# miniPCIE_Connector.net
KiCad netlist of a schematic drawn in Altium Designer
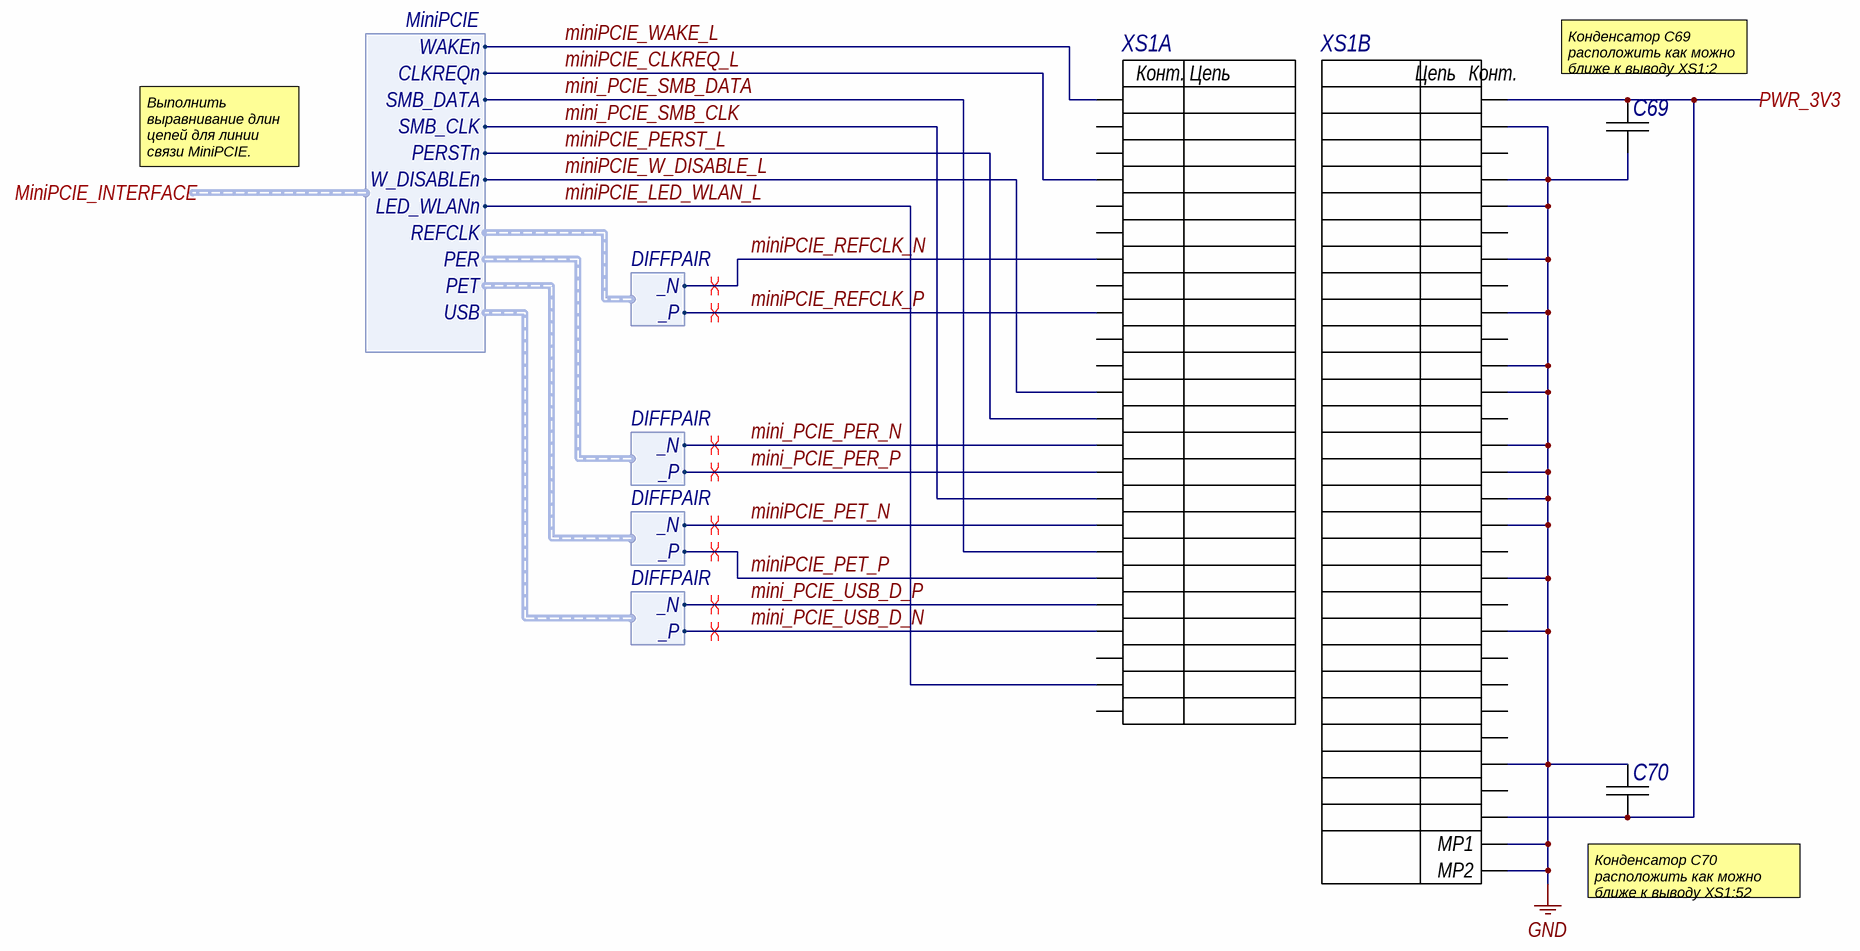
[diagram p0: miniPCIE Connector.SchDoc]

(export (version "E")
  (design (tool "Eeschema 10.0.6"))
  (components
    (comp (ref "C69")
      (value "C1005X7R1E104M")
      (footprint "CAPC1005X55X10LL05")
      (description "Chip Capacitor, 0.1 uF, +/- 20%, 25 V, -55 to 125 degC, 0402 (1005 Metric), RoHS, Tape and Reel")
      (fields (field (name "TOLERANCE") "20%"))
      (libsource (lib "MiniPC DB") (part "CAP_NP"))
    )
    (comp (ref "C70")
      (value "C1005X7R1E104M")
      (footprint "CAPC1005X55X10LL05")
      (description "Chip Capacitor, 0.1 uF, +/- 20%, 25 V, -55 to 125 degC, 0402 (1005 Metric), RoHS, Tape and Reel")
      (fields (field (name "TOLERANCE") "20%"))
      (libsource (lib "MiniPC DB") (part "CAP_NP"))
    )
    (comp (ref "XS1")
      (value "292443-1")
      (footprint "BTB-SM0-8-2H52F")
      (description "Board-to-Board Connector, SMT, Right Angle, Pitch 0.8mm, 52-Position, Female")
      (fields (field (name "PUBLISHER") "Altium"))
      (libsource (lib "MiniPC DB") (part "MINIPCIEXPRESS"))
    )
  )
  (nets
    (net (code "4") (name "/PWR_3V3") (class "Default")
      (node (ref "C69") (pin "2") (pinfunction "2_2") (pintype "passive"))
      (node (ref "C70") (pin "1") (pinfunction "1_1") (pintype "passive"))
      (node (ref "XS1") (pin "2") (pinfunction "3,3Vaux_2") (pintype "passive"))
      (node (ref "XS1") (pin "52") (pinfunction "3,3Vaux_52") (pintype "passive"))
    )
    (net (code "5") (name "/miniPCIE_CLKREQ_L") (class "Default")
      (node (ref "XS1") (pin "7") (pinfunction "CLKREQ#_7") (pintype "passive"))
    )
    (net (code "6") (name "/miniPCIE_LED_WLAN_L") (class "Default")
      (node (ref "XS1") (pin "44") (pinfunction "LED_WLAN#_44") (pintype "passive"))
    )
    (net (code "7") (name "/miniPCIE_PERST_L") (class "Default")
      (node (ref "XS1") (pin "22") (pinfunction "PERST#_22") (pintype "passive"))
    )
    (net (code "8") (name "/miniPCIE_PET_N") (class "Default")
      (node (ref "XS1") (pin "31") (pinfunction "PETnO_31") (pintype "passive"))
    )
    (net (code "9") (name "/miniPCIE_PET_P") (class "Default")
      (node (ref "XS1") (pin "33") (pinfunction "PETpO_33") (pintype "passive"))
    )
    (net (code "10") (name "/miniPCIE_REFCLK_N") (class "Default")
      (node (ref "XS1") (pin "11") (pinfunction "REFCLK-_11") (pintype "passive"))
    )
    (net (code "11") (name "/miniPCIE_REFCLK_P") (class "Default")
      (node (ref "XS1") (pin "13") (pinfunction "REFCLK_+_13") (pintype "passive"))
    )
    (net (code "12") (name "/miniPCIE_WAKE_L") (class "Default")
      (node (ref "XS1") (pin "1") (pinfunction "WAKE#_1") (pintype "passive"))
    )
    (net (code "13") (name "/miniPCIE_W_DISABLE_L") (class "Default")
      (node (ref "XS1") (pin "20") (pinfunction "W.DISABLE#_20") (pintype "passive"))
    )
    (net (code "14") (name "/mini_PCIE_PER_N") (class "Default")
      (node (ref "XS1") (pin "23") (pinfunction "PERnO_23") (pintype "passive"))
    )
    (net (code "15") (name "/mini_PCIE_PER_P") (class "Default")
      (node (ref "XS1") (pin "25") (pinfunction "PERpO_25") (pintype "passive"))
    )
    (net (code "16") (name "/mini_PCIE_SMB_CLK") (class "Default")
      (node (ref "XS1") (pin "30") (pinfunction "SMB_CLK_30") (pintype "passive"))
    )
    (net (code "17") (name "/mini_PCIE_SMB_DATA") (class "Default")
      (node (ref "XS1") (pin "32") (pinfunction "SM8_DATA_32") (pintype "passive"))
    )
    (net (code "18") (name "/mini_PCIE_USB_D_N") (class "Default")
      (node (ref "XS1") (pin "38") (pinfunction "USB_D+_38") (pintype "passive"))
    )
    (net (code "19") (name "/mini_PCIE_USB_D_P") (class "Default")
      (node (ref "XS1") (pin "36") (pinfunction "USB_D-_36") (pintype "passive"))
    )
    (net (code "21") (name "GND") (class "Default")
      (node (ref "C69") (pin "1") (pinfunction "1_1") (pintype "passive"))
      (node (ref "C70") (pin "2") (pinfunction "2_2") (pintype "passive"))
      (node (ref "XS1") (pin "15") (pinfunction "GND_15") (pintype "passive"))
      (node (ref "XS1") (pin "18") (pinfunction "GND_18") (pintype "passive"))
      (node (ref "XS1") (pin "21") (pinfunction "GND_21") (pintype "passive"))
      (node (ref "XS1") (pin "26") (pinfunction "GND_26") (pintype "passive"))
      (node (ref "XS1") (pin "27") (pinfunction "GND_27") (pintype "passive"))
      (node (ref "XS1") (pin "29") (pinfunction "GND_29") (pintype "passive"))
      (node (ref "XS1") (pin "34") (pinfunction "GND_34") (pintype "passive"))
      (node (ref "XS1") (pin "35") (pinfunction "GND_35") (pintype "passive"))
      (node (ref "XS1") (pin "37") (pinfunction "GND_37") (pintype "passive"))
      (node (ref "XS1") (pin "4") (pinfunction "GND_4") (pintype "passive"))
      (node (ref "XS1") (pin "40") (pinfunction "GND_40") (pintype "passive"))
      (node (ref "XS1") (pin "43") (pinfunction "GND_43") (pintype "passive"))
      (node (ref "XS1") (pin "50") (pinfunction "GND_50") (pintype "passive"))
      (node (ref "XS1") (pin "9") (pinfunction "GND_9") (pintype "passive"))
      (node (ref "XS1") (pin "MP1") (pinfunction "MP1_MP1") (pintype "passive"))
      (node (ref "XS1") (pin "MP2") (pinfunction "MP2_MP2") (pintype "passive"))
    )
    (net (code "22") (name "unconnected-(XS1A-COEX2-Pad5)") (class "Default")
      (node (ref "XS1") (pin "5") (pinfunction "COEX2_5") (pintype "passive"))
    )
    (net (code "23") (name "unconnected-(XS1A-COE_XI-Pad3)") (class "Default")
      (node (ref "XS1") (pin "3") (pinfunction "COE_XI_3") (pintype "passive"))
    )
    (net (code "24") (name "unconnected-(XS1A-LED.WWAN#-Pad42)") (class "Default")
      (node (ref "XS1") (pin "42") (pinfunction "LED.WWAN#_42") (pintype "passive"))
    )
    (net (code "25") (name "unconnected-(XS1A-LED_WPAN#-Pad46)") (class "Default")
      (node (ref "XS1") (pin "46") (pinfunction "LED_WPAN#_46") (pintype "passive"))
    )
    (net (code "26") (name "unconnected-(XS1A-UIM.PWR-Pad8)") (class "Default")
      (node (ref "XS1") (pin "8") (pinfunction "UIM.PWR_8") (pintype "passive"))
    )
    (net (code "27") (name "unconnected-(XS1A-UIM.RESET-Pad14)") (class "Default")
      (node (ref "XS1") (pin "14") (pinfunction "UIM.RESET_14") (pintype "passive"))
    )
    (net (code "28") (name "unconnected-(XS1A-UIM_CLK-Pad12)") (class "Default")
      (node (ref "XS1") (pin "12") (pinfunction "UIM_CLK_12") (pintype "passive"))
    )
    (net (code "29") (name "unconnected-(XS1A-UIM_DATA-Pad10)") (class "Default")
      (node (ref "XS1") (pin "10") (pinfunction "UIM_DATA_10") (pintype "passive"))
    )
    (net (code "30") (name "unconnected-(XS1A-UIM_VPP-Pad16)") (class "Default")
      (node (ref "XS1") (pin "16") (pinfunction "UIM_VPP_16") (pintype "passive"))
    )
    (net (code "31") (name "unconnected-(XS1B-1,5V-Pad6)") (class "Default")
      (node (ref "XS1") (pin "6") (pinfunction "1,5V_6") (pintype "passive"))
    )
    (net (code "32") (name "unconnected-(XS1B-1,5V-Pad28)") (class "Default")
      (node (ref "XS1") (pin "28") (pinfunction "1,5V_28") (pintype "passive"))
    )
    (net (code "33") (name "unconnected-(XS1B-1,5V-Pad48)") (class "Default")
      (node (ref "XS1") (pin "48") (pinfunction "1,5V_48") (pintype "passive"))
    )
    (net (code "34") (name "unconnected-(XS1B-3,3Vaux-Pad24)") (class "Default")
      (node (ref "XS1") (pin "24") (pinfunction "3,3Vaux_24") (pintype "passive"))
    )
    (net (code "35") (name "unconnected-(XS1B-3,3Vaux-Pad39)") (class "Default")
      (node (ref "XS1") (pin "39") (pinfunction "3,3Vaux_39") (pintype "passive"))
    )
    (net (code "36") (name "unconnected-(XS1B-3,3Vaux-Pad41)") (class "Default")
      (node (ref "XS1") (pin "41") (pinfunction "3,3Vaux_41") (pintype "passive"))
    )
    (net (code "37") (name "unconnected-(XS1B-Reserved-Pad17)") (class "Default")
      (node (ref "XS1") (pin "17") (pinfunction "Reserved_17") (pintype "passive"))
    )
    (net (code "38") (name "unconnected-(XS1B-Reserved-Pad19)") (class "Default")
      (node (ref "XS1") (pin "19") (pinfunction "Reserved_19") (pintype "passive"))
    )
    (net (code "39") (name "unconnected-(XS1B-Reserved-Pad45)") (class "Default")
      (node (ref "XS1") (pin "45") (pinfunction "Reserved_45") (pintype "passive"))
    )
    (net (code "40") (name "unconnected-(XS1B-Reserved-Pad47)") (class "Default")
      (node (ref "XS1") (pin "47") (pinfunction "Reserved_47") (pintype "passive"))
    )
    (net (code "41") (name "unconnected-(XS1B-Reserved-Pad49)") (class "Default")
      (node (ref "XS1") (pin "49") (pinfunction "Reserved_49") (pintype "passive"))
    )
    (net (code "42") (name "unconnected-(XS1B-Reserved-Pad51)") (class "Default")
      (node (ref "XS1") (pin "51") (pinfunction "Reserved_51") (pintype "passive"))
    )
  )
)
